# USB2SPI.net
KiCad netlist of a schematic drawn in EasyEDA Pro
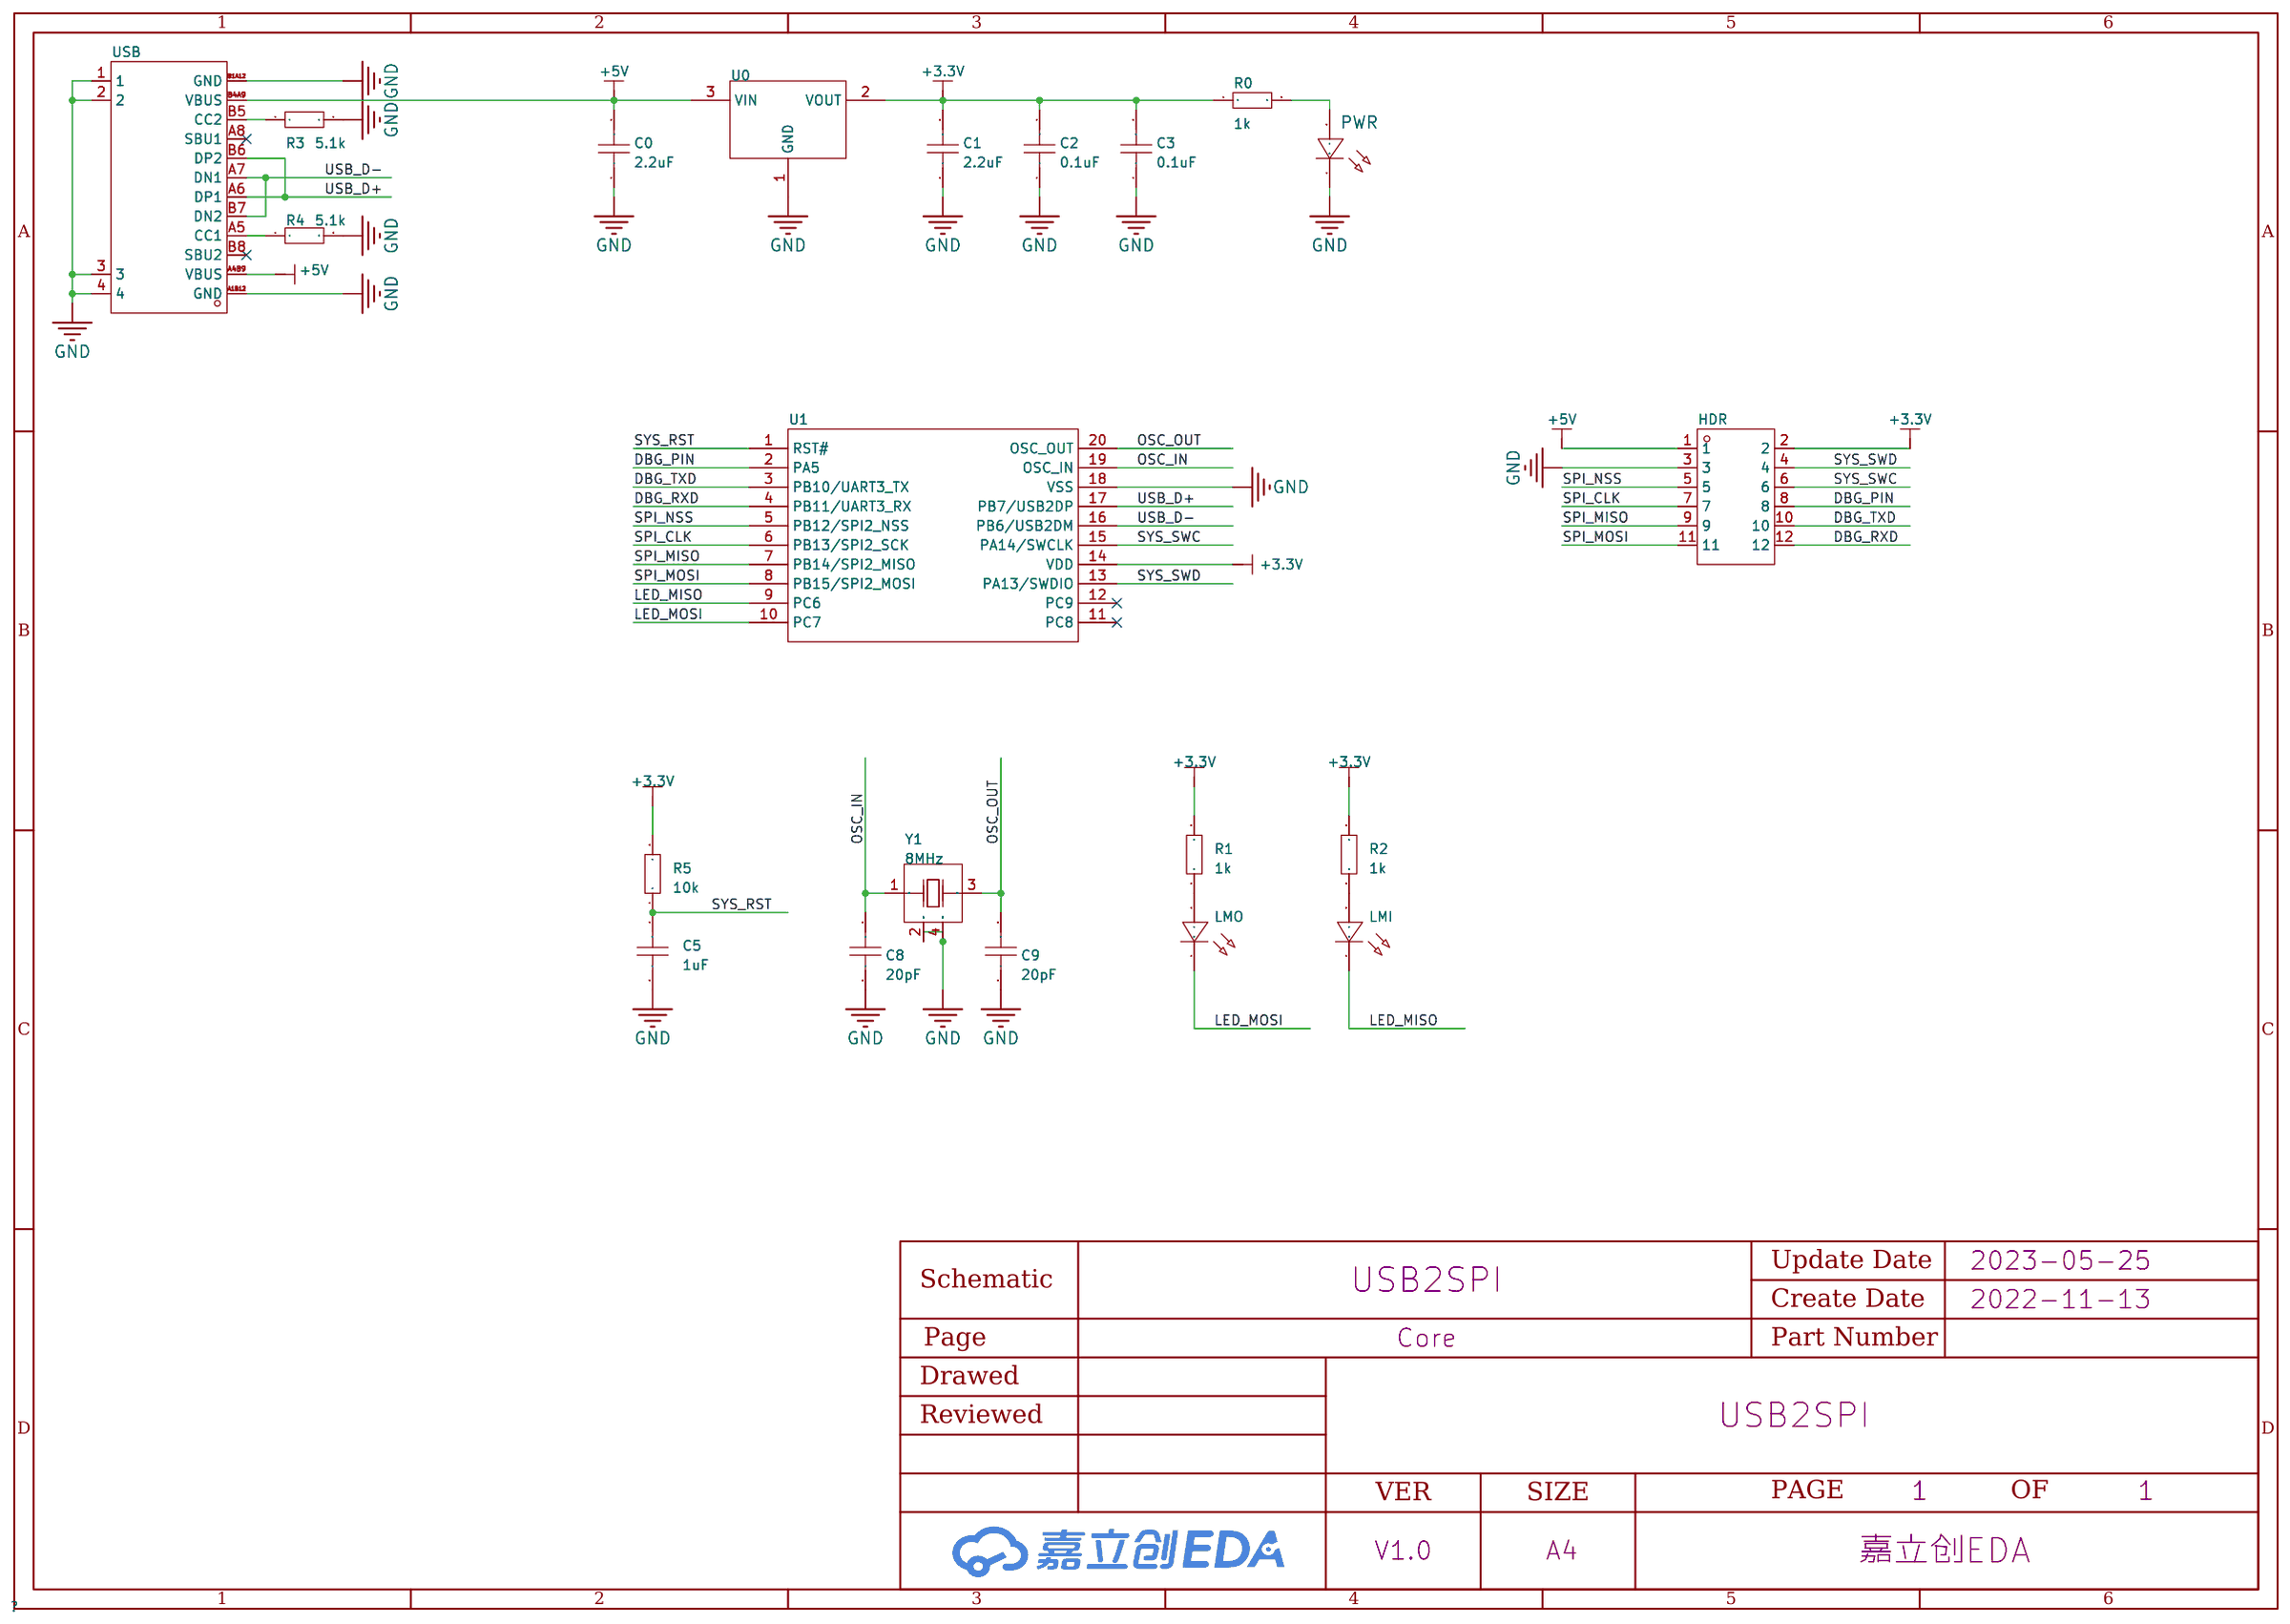
[diagram p0: schematic sheet]

(export (version "E")
  (design (tool "Eeschema 10.0.6"))
  (components
    (comp (ref "C0")
      (value "2.2uF")
      (footprint "easyedapro:C0603")
      (description "容值:100nF;精度:±10%;额定电压:50V;温度系数:X7R;")
      (libsource (lib "easyedapro") (part "C1210X7R475K630NT"))
    )
    (comp (ref "C1")
      (value "2.2uF")
      (footprint "easyedapro:C0603")
      (description "容值:100nF;精度:±10%;额定电压:50V;温度系数:X7R;")
      (libsource (lib "easyedapro") (part "C1210X7R475K630NT"))
    )
    (comp (ref "C2")
      (value "0.1uF")
      (footprint "easyedapro:C0603")
      (description "容值:100nF;精度:±10%;额定电压:50V;温度系数:X7R;")
      (libsource (lib "easyedapro") (part "C1210X7R475K630NT"))
    )
    (comp (ref "C3")
      (value "0.1uF")
      (footprint "easyedapro:C0603")
      (description "容值:100nF;精度:±10%;额定电压:50V;温度系数:X7R;")
      (libsource (lib "easyedapro") (part "C1210X7R475K630NT"))
    )
    (comp (ref "C5")
      (value "1uF")
      (footprint "easyedapro:C0603")
      (description "容值:100nF;精度:±10%;额定电压:50V;温度系数:X7R;")
      (libsource (lib "easyedapro") (part "C1210X7R475K630NT"))
    )
    (comp (ref "C8")
      (value "20pF")
      (footprint "easyedapro:C0603")
      (description "容值:100nF;精度:±10%;额定电压:50V;温度系数:X7R;")
      (libsource (lib "easyedapro") (part "C1210X7R475K630NT"))
    )
    (comp (ref "C9")
      (value "20pF")
      (footprint "easyedapro:C0603")
      (description "容值:100nF;精度:±10%;额定电压:50V;温度系数:X7R;")
      (libsource (lib "easyedapro") (part "C1210X7R475K630NT"))
    )
    (comp (ref "HDR")
      (value "~")
      (footprint "easyedapro:HDR-SMD_2X6P-P2.54")
      (libsource (lib "easyedapro") (part "HDR-M-2.54_2x6"))
    )
    (comp (ref "LMI")
      (value "~")
      (footprint "easyedapro:LED0603-RD")
      (description "照明颜色:翠绿;色温 - CCT（K）:-;主波长/色坐标:520~535nm;")
      (libsource (lib "easyedapro") (part "LED_G"))
    )
    (comp (ref "LMO")
      (value "~")
      (footprint "easyedapro:LED0603-RD")
      (description "照明颜色:翠绿;色温 - CCT（K）:-;主波长/色坐标:520~535nm;")
      (libsource (lib "easyedapro") (part "LED_G"))
    )
    (comp (ref "PWR")
      (value "~")
      (footprint "easyedapro:LED0603-RD_BLUE")
      (libsource (lib "easyedapro") (part "LED_R"))
    )
    (comp (ref "R0") (value "1k") (footprint "easyedapro:R0603") (libsource (lib "easyedapro") (part "电阻")))
    (comp (ref "R1") (value "1k") (footprint "easyedapro:R0603") (libsource (lib "easyedapro") (part "电阻")))
    (comp (ref "R2") (value "1k") (footprint "easyedapro:R0603") (libsource (lib "easyedapro") (part "电阻")))
    (comp (ref "R3") (value "5.1k") (footprint "easyedapro:R0603") (libsource (lib "easyedapro") (part "电阻")))
    (comp (ref "R4") (value "5.1k") (footprint "easyedapro:R0603") (libsource (lib "easyedapro") (part "电阻")))
    (comp (ref "R5") (value "10k") (footprint "easyedapro:R0603") (libsource (lib "easyedapro") (part "电阻")))
    (comp (ref "U0")
      (value "HT7233")
      (footprint "easyedapro:SOT-23-3_L2.9-W1.6-P1.90-LS2.8-BR")
      (fields (field (name "Manufacturer") "HOLTEK(台湾合泰/盛群)"))
      (libsource (lib "easyedapro") (part "HT7233"))
    )
    (comp (ref "U1")
      (value "~")
      (footprint "easyedapro:TSSOP-20_L6.5-W4.4-P0.65-LS6.4-BL")
      (libsource (lib "easyedapro") (part "CH32V305FBP6"))
    )
    (comp (ref "USB")
      (value "USB-TYPE-C-017")
      (footprint "easyedapro:USB-TYPE-C-SMD_C9900008089")
      (description "连接器类型:Type-C;标准:-;公母:母座;触点数量:16;端口数量:1;安装方式:卧贴;额定电流 - 电源:3A;工作温度范围:-25~+85;")
      (fields (field (name "Manufacturer") "DEALON(德艺隆)"))
      (libsource (lib "easyedapro") (part "USB-TYPE-C-017"))
    )
    (comp (ref "Y1")
      (value "8MHz")
      (footprint "easyedapro:OSC-SMD_4P-L3.2-W2.5-BL")
      (description "晶振类型:贴片无源晶振;频率:12MHz;频率公差:±10ppm;频率稳定度:±30ppm;负载电容:20pF;工作温度:-40~+85;")
      (fields (field (name "Manufacturer Part") "X322512MSB4SI") (field (name "Manufacturer") "YXC(扬兴晶振)"))
      (libsource (lib "easyedapro") (part "X322512MSB4SI"))
    )
  )
  (nets
    (net (code "1") (name "+3.3V") (class "Default")
      (node (ref "C1") (pin "2") (pinfunction "2_2") (pintype "input"))
      (node (ref "C2") (pin "2") (pinfunction "2_2") (pintype "input"))
      (node (ref "C3") (pin "2") (pinfunction "2_2") (pintype "input"))
      (node (ref "HDR") (pin "2") (pinfunction "2_2") (pintype "input"))
      (node (ref "R0") (pin "1") (pinfunction "1_1") (pintype "input"))
      (node (ref "R1") (pin "2") (pinfunction "2_2") (pintype "input"))
      (node (ref "R2") (pin "2") (pinfunction "2_2") (pintype "input"))
      (node (ref "R5") (pin "2") (pinfunction "2_2") (pintype "input"))
      (node (ref "U0") (pin "2") (pinfunction "VOUT_2") (pintype "input"))
      (node (ref "U1") (pin "14") (pinfunction "VDD_14") (pintype "input"))
    )
    (net (code "2") (name "+5V") (class "Default")
      (node (ref "C0") (pin "2") (pinfunction "2_2") (pintype "input"))
      (node (ref "HDR") (pin "1") (pinfunction "1_1") (pintype "input"))
      (node (ref "U0") (pin "3") (pinfunction "VIN_3") (pintype "input"))
      (node (ref "USB") (pin "A4B9") (pinfunction "VBUS_A4B9") (pintype "input"))
      (node (ref "USB") (pin "B4A9") (pinfunction "VBUS_B4A9") (pintype "input"))
    )
    (net (code "3") (name "/DBG_PIN") (class "Default")
      (node (ref "HDR") (pin "8") (pinfunction "8_8") (pintype "input"))
      (node (ref "U1") (pin "2") (pinfunction "PA5_2") (pintype "input"))
    )
    (net (code "4") (name "/DBG_RXD") (class "Default")
      (node (ref "HDR") (pin "12") (pinfunction "12_12") (pintype "input"))
      (node (ref "U1") (pin "4") (pinfunction "PB11/UART3_RX_4") (pintype "input"))
    )
    (net (code "5") (name "/DBG_TXD") (class "Default")
      (node (ref "HDR") (pin "10") (pinfunction "10_10") (pintype "input"))
      (node (ref "U1") (pin "3") (pinfunction "PB10/UART3_TX_3") (pintype "input"))
    )
    (net (code "6") (name "/LED_MISO") (class "Default")
      (node (ref "LMI") (pin "1") (pinfunction "C_1") (pintype "input"))
      (node (ref "U1") (pin "9") (pinfunction "PC6_9") (pintype "input"))
    )
    (net (code "7") (name "/LED_MOSI") (class "Default")
      (node (ref "LMO") (pin "1") (pinfunction "C_1") (pintype "input"))
      (node (ref "U1") (pin "10") (pinfunction "PC7_10") (pintype "input"))
    )
    (net (code "8") (name "/OSC_IN") (class "Default")
      (node (ref "C8") (pin "1") (pinfunction "1_1") (pintype "input"))
      (node (ref "U1") (pin "19") (pinfunction "OSC_IN_19") (pintype "input"))
      (node (ref "Y1") (pin "1") (pinfunction "OSC1_1") (pintype "input"))
    )
    (net (code "9") (name "/OSC_OUT") (class "Default")
      (node (ref "C9") (pin "2") (pinfunction "2_2") (pintype "input"))
      (node (ref "U1") (pin "20") (pinfunction "OSC_OUT_20") (pintype "input"))
      (node (ref "Y1") (pin "3") (pinfunction "OSC2_3") (pintype "input"))
    )
    (net (code "10") (name "/SPI_CLK") (class "Default")
      (node (ref "HDR") (pin "7") (pinfunction "7_7") (pintype "input"))
      (node (ref "U1") (pin "6") (pinfunction "PB13/SPI2_SCK_6") (pintype "input"))
    )
    (net (code "11") (name "/SPI_MISO") (class "Default")
      (node (ref "HDR") (pin "9") (pinfunction "9_9") (pintype "input"))
      (node (ref "U1") (pin "7") (pinfunction "PB14/SPI2_MISO_7") (pintype "input"))
    )
    (net (code "12") (name "/SPI_MOSI") (class "Default")
      (node (ref "HDR") (pin "11") (pinfunction "11_11") (pintype "input"))
      (node (ref "U1") (pin "8") (pinfunction "PB15/SPI2_MOSI_8") (pintype "input"))
    )
    (net (code "13") (name "/SPI_NSS") (class "Default")
      (node (ref "HDR") (pin "5") (pinfunction "5_5") (pintype "input"))
      (node (ref "U1") (pin "5") (pinfunction "PB12/SPI2_NSS_5") (pintype "input"))
    )
    (net (code "14") (name "/SYS_RST") (class "Default")
      (node (ref "C5") (pin "1") (pinfunction "1_1") (pintype "input"))
      (node (ref "R5") (pin "1") (pinfunction "1_1") (pintype "input"))
      (node (ref "U1") (pin "1") (pinfunction "RST#_1") (pintype "input"))
    )
    (net (code "15") (name "/SYS_SWC") (class "Default")
      (node (ref "HDR") (pin "6") (pinfunction "6_6") (pintype "input"))
      (node (ref "U1") (pin "15") (pinfunction "PA14/SWCLK_15") (pintype "input"))
    )
    (net (code "16") (name "/SYS_SWD") (class "Default")
      (node (ref "HDR") (pin "4") (pinfunction "4_4") (pintype "input"))
      (node (ref "U1") (pin "13") (pinfunction "PA13/SWDIO_13") (pintype "input"))
    )
    (net (code "17") (name "/USB_D+") (class "Default")
      (node (ref "U1") (pin "17") (pinfunction "PB7/USB2DP_17") (pintype "input"))
      (node (ref "USB") (pin "A6") (pinfunction "DP1_A6") (pintype "input"))
      (node (ref "USB") (pin "B6") (pinfunction "DP2_B6") (pintype "input"))
    )
    (net (code "18") (name "/USB_D-") (class "Default")
      (node (ref "U1") (pin "16") (pinfunction "PB6/USB2DM_16") (pintype "input"))
      (node (ref "USB") (pin "A7") (pinfunction "DN1_A7") (pintype "input"))
      (node (ref "USB") (pin "B7") (pinfunction "DN2_B7") (pintype "input"))
    )
    (net (code "19") (name "GND") (class "Default")
      (node (ref "C0") (pin "1") (pinfunction "1_1") (pintype "input"))
      (node (ref "C1") (pin "1") (pinfunction "1_1") (pintype "input"))
      (node (ref "C2") (pin "1") (pinfunction "1_1") (pintype "input"))
      (node (ref "C3") (pin "1") (pinfunction "1_1") (pintype "input"))
      (node (ref "C5") (pin "2") (pinfunction "2_2") (pintype "input"))
      (node (ref "C8") (pin "2") (pinfunction "2_2") (pintype "input"))
      (node (ref "C9") (pin "1") (pinfunction "1_1") (pintype "input"))
      (node (ref "HDR") (pin "3") (pinfunction "3_3") (pintype "input"))
      (node (ref "PWR") (pin "1") (pinfunction "C_1") (pintype "input"))
      (node (ref "R3") (pin "2") (pinfunction "2_2") (pintype "input"))
      (node (ref "R4") (pin "2") (pinfunction "2_2") (pintype "input"))
      (node (ref "U0") (pin "1") (pinfunction "GND_1") (pintype "input"))
      (node (ref "U1") (pin "18") (pinfunction "VSS_18") (pintype "input"))
      (node (ref "USB") (pin "1") (pinfunction "1_1") (pintype "input"))
      (node (ref "USB") (pin "2") (pinfunction "2_2") (pintype "input"))
      (node (ref "USB") (pin "3") (pinfunction "3_3") (pintype "input"))
      (node (ref "USB") (pin "4") (pinfunction "4_4") (pintype "input"))
      (node (ref "USB") (pin "A1B12") (pinfunction "GND_A1B12") (pintype "input"))
      (node (ref "USB") (pin "B1A12") (pinfunction "GND_B1A12") (pintype "input"))
      (node (ref "Y1") (pin "2") (pinfunction "GND_2") (pintype "input"))
      (node (ref "Y1") (pin "4") (pinfunction "GND_4") (pintype "input"))
    )
    (net (code "20") (name "Net-(LMI-A)") (class "Default")
      (node (ref "LMI") (pin "2") (pinfunction "A_2") (pintype "input"))
      (node (ref "R2") (pin "1") (pinfunction "1_1") (pintype "input"))
    )
    (net (code "21") (name "Net-(LMO-A)") (class "Default")
      (node (ref "LMO") (pin "2") (pinfunction "A_2") (pintype "input"))
      (node (ref "R1") (pin "1") (pinfunction "1_1") (pintype "input"))
    )
    (net (code "22") (name "Net-(PWR-A)") (class "Default")
      (node (ref "PWR") (pin "2") (pinfunction "A_2") (pintype "input"))
      (node (ref "R0") (pin "2") (pinfunction "2_2") (pintype "input"))
    )
    (net (code "23") (name "Net-(USB-CC1)") (class "Default")
      (node (ref "R4") (pin "1") (pinfunction "1_1") (pintype "input"))
      (node (ref "USB") (pin "A5") (pinfunction "CC1_A5") (pintype "input"))
    )
    (net (code "24") (name "Net-(USB-CC2)") (class "Default")
      (node (ref "R3") (pin "1") (pinfunction "1_1") (pintype "input"))
      (node (ref "USB") (pin "B5") (pinfunction "CC2_B5") (pintype "input"))
    )
    (net (code "25") (name "unconnected-(U1-PC8-Pad11)") (class "Default")
      (node (ref "U1") (pin "11") (pinfunction "PC8_11") (pintype "input+no_connect"))
    )
    (net (code "26") (name "unconnected-(U1-PC9-Pad12)") (class "Default")
      (node (ref "U1") (pin "12") (pinfunction "PC9_12") (pintype "input+no_connect"))
    )
    (net (code "27") (name "unconnected-(USB-SBU1-PadA8)") (class "Default")
      (node (ref "USB") (pin "A8") (pinfunction "SBU1_A8") (pintype "input+no_connect"))
    )
    (net (code "28") (name "unconnected-(USB-SBU2-PadB8)") (class "Default")
      (node (ref "USB") (pin "B8") (pinfunction "SBU2_B8") (pintype "input+no_connect"))
    )
  )
)
